# n-watch_v2_0_2022-03-19.net
KiCad netlist of a schematic drawn in Altium Designer
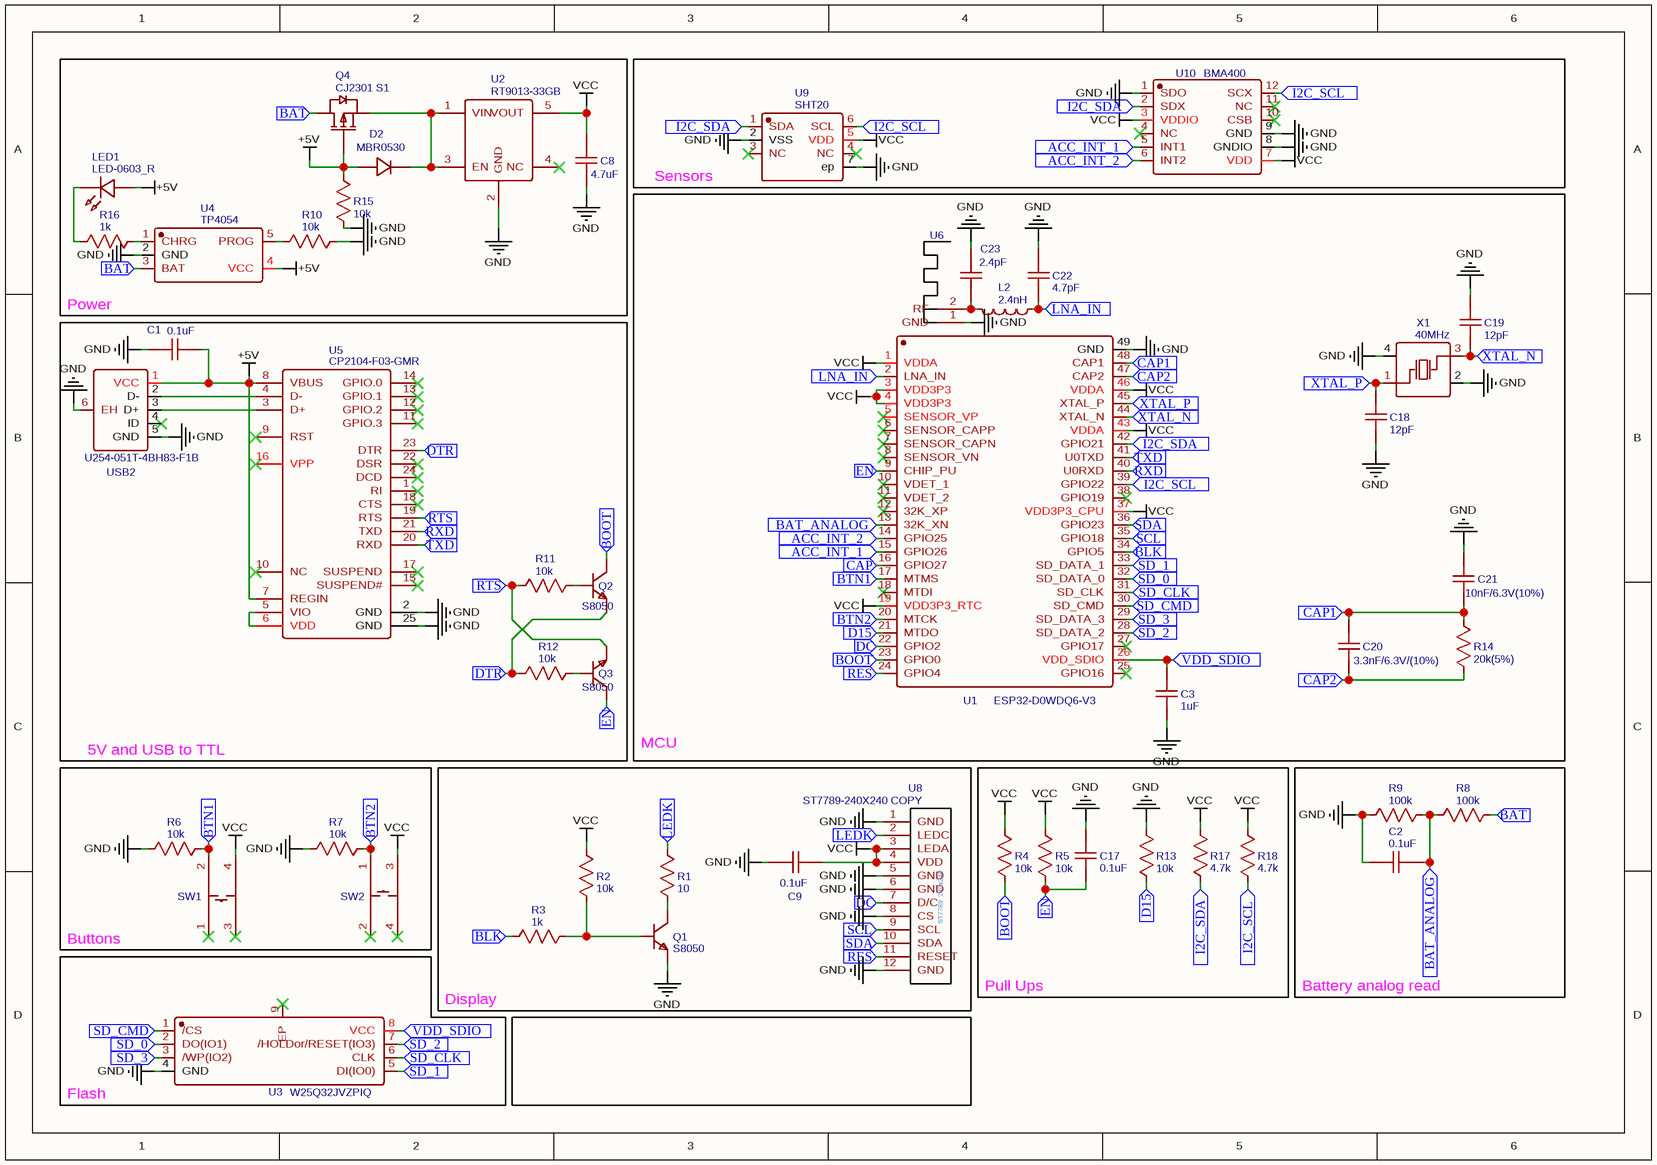
[diagram p0: n-watch v2.0_2022-03-19.schdoc]

(export (version "E")
  (design (tool "Eeschema 10.0.6"))
  (components
    (comp (ref "C1")
      (value "0.1uF")
      (fields (field (name "CONTRIBUTOR") "LCEDA_Lib"))
      (libsource (lib "altium-import") (part "root_2_0.1uF_"))
    )
    (comp (ref "C2")
      (value "0.1uF")
      (fields (field (name "CONTRIBUTOR") "LCEDA_Lib"))
      (libsource (lib "") (part "root_0_0.1uF__1"))
    )
    (comp (ref "C3")
      (value "1uF")
      (fields (field (name "CONTRIBUTOR") "LCEDA_Lib"))
      (libsource (lib "altium-import") (part "root_1_1uF_"))
    )
    (comp (ref "C8")
      (value "4.7uF")
      (fields (field (name "CONTRIBUTOR") "LCEDA_Lib"))
      (libsource (lib "altium-import") (part "root_1_4.7uF_"))
    )
    (comp (ref "C9")
      (value "0.1uF")
      (fields (field (name "CONTRIBUTOR") "LCEDA_Lib"))
      (libsource (lib "altium-import") (part "root_0_0.1uF_"))
    )
    (comp (ref "C17")
      (value "0.1uF")
      (fields (field (name "CONTRIBUTOR") "LCEDA_Lib"))
      (libsource (lib "altium-import") (part "root_1_0.1uF_"))
    )
    (comp (ref "C18")
      (value "12pF")
      (fields (field (name "CONTRIBUTOR") "LCEDA_Lib"))
      (libsource (lib "altium-import") (part "root_1_12pF_"))
    )
    (comp (ref "C19")
      (value "12pF")
      (fields (field (name "CONTRIBUTOR") "LCEDA_Lib"))
      (libsource (lib "altium-import") (part "root_1_12pF_"))
    )
    (comp (ref "C20")
      (value "3.3nF/6.3V/(10%)")
      (fields (field (name "CONTRIBUTOR") "LCEDA_Lib"))
      (libsource (lib "altium-import") (part "root_1_3.3nF/6.3V/(10%)_"))
    )
    (comp (ref "C21")
      (value "10nF/6.3V(10%)")
      (fields (field (name "CONTRIBUTOR") "LCEDA_Lib"))
      (libsource (lib "altium-import") (part "root_1_10nF/6.3V(10%)_"))
    )
    (comp (ref "C22")
      (value "4.7pF")
      (fields (field (name "CONTRIBUTOR") "LCEDA_Lib"))
      (libsource (lib "altium-import") (part "root_3_4.7pF_"))
    )
    (comp (ref "C23")
      (value "2.4pF")
      (fields (field (name "CONTRIBUTOR") "LCEDA_Lib"))
      (libsource (lib "altium-import") (part "root_1_2.4pF_"))
    )
    (comp (ref "D2")
      (value "MBR0530")
      (fields (field (name "BOM_SUPPLIER PART") "C77336"))
      (libsource (lib "altium-import") (part "root_2_MBR0530_"))
    )
    (comp (ref "L2")
      (value "2.4nH")
      (fields (field (name "CONTRIBUTOR") "LCEDA_Lib"))
      (libsource (lib "altium-import") (part "root_2_2.4nH_"))
    )
    (comp (ref "LED1")
      (value "LED-0603_R")
      (fields
        (field (name "BOM_MANUFACTURER PART") "19-217/R6C-AL1M2VY/3T")
        (field (name "BOM_SUPPLIER PART") "C72044")
        (field (name "CONTRIBUTOR") "LCEDA_01")
      )
      (libsource (lib "altium-import") (part "root_2_LED-0603_R_"))
    )
    (comp (ref "Q1")
      (value "S8050")
      (fields (field (name "BOM_SUPPLIER PART") "C916390") (field (name "CONTRIBUTOR") "LCSC"))
      (libsource (lib "altium-import") (part "root_0_S8050_"))
    )
    (comp (ref "Q2")
      (value "S8050")
      (fields (field (name "BOM_SUPPLIER PART") "C916390") (field (name "CONTRIBUTOR") "LCSC"))
      (libsource (lib "altium-import") (part "root_0_S8050_"))
    )
    (comp (ref "Q3")
      (value "S8050")
      (fields (field (name "BOM_SUPPLIER PART") "C916390") (field (name "CONTRIBUTOR") "LCSC"))
      (libsource (lib "") (part "root_0_S8050__1"))
    )
    (comp (ref "Q4")
      (value "CJ2301 S1")
      (fields (field (name "BOM_SUPPLIER PART") "C8547"))
      (libsource (lib "altium-import") (part "root_1_CJ2301 S1_"))
    )
    (comp (ref "R1")
      (value "10")
      (fields (field (name "CONTRIBUTOR") "LCEDA_Lib"))
      (libsource (lib "altium-import") (part "root_1_10_"))
    )
    (comp (ref "R2")
      (value "10k")
      (fields (field (name "CONTRIBUTOR") "LCEDA_Lib"))
      (libsource (lib "altium-import") (part "root_1_10k_"))
    )
    (comp (ref "R3")
      (value "1k")
      (fields (field (name "CONTRIBUTOR") "LCEDA_Lib"))
      (libsource (lib "altium-import") (part "root_2_1k_"))
    )
    (comp (ref "R4")
      (value "10k")
      (fields (field (name "CONTRIBUTOR") "LCEDA_Lib"))
      (libsource (lib "altium-import") (part "root_1_10k_"))
    )
    (comp (ref "R5")
      (value "10k")
      (fields (field (name "CONTRIBUTOR") "LCEDA_Lib"))
      (libsource (lib "altium-import") (part "root_1_10k_"))
    )
    (comp (ref "R6")
      (value "10k")
      (fields (field (name "CONTRIBUTOR") "LCEDA_Lib"))
      (libsource (lib "altium-import") (part "root_0_10k_"))
    )
    (comp (ref "R7")
      (value "10k")
      (fields (field (name "CONTRIBUTOR") "LCEDA_Lib"))
      (libsource (lib "altium-import") (part "root_0_10k_"))
    )
    (comp (ref "R8")
      (value "100k")
      (fields (field (name "CONTRIBUTOR") "LCEDA_Lib"))
      (libsource (lib "altium-import") (part "root_2_100k_"))
    )
    (comp (ref "R9")
      (value "100k")
      (fields (field (name "CONTRIBUTOR") "LCEDA_Lib"))
      (libsource (lib "altium-import") (part "root_2_100k_"))
    )
    (comp (ref "R10")
      (value "10k")
      (fields (field (name "CONTRIBUTOR") "LCEDA_Lib"))
      (libsource (lib "altium-import") (part "root_0_10k_"))
    )
    (comp (ref "R11")
      (value "10k")
      (fields (field (name "CONTRIBUTOR") "LCEDA_Lib"))
      (libsource (lib "altium-import") (part "root_2_10k_"))
    )
    (comp (ref "R12")
      (value "10k")
      (fields (field (name "CONTRIBUTOR") "LCEDA_Lib"))
      (libsource (lib "altium-import") (part "root_0_10k_"))
    )
    (comp (ref "R13")
      (value "10k")
      (fields (field (name "CONTRIBUTOR") "LCEDA_Lib"))
      (libsource (lib "altium-import") (part "root_1_10k_"))
    )
    (comp (ref "R14")
      (value "20k(5%)")
      (fields (field (name "CONTRIBUTOR") "LCEDA_Lib"))
      (libsource (lib "altium-import") (part "root_1_20k(5%)_"))
    )
    (comp (ref "R15")
      (value "10k")
      (fields (field (name "CONTRIBUTOR") "LCEDA_Lib"))
      (libsource (lib "altium-import") (part "root_1_10k_"))
    )
    (comp (ref "R16")
      (value "1k")
      (fields (field (name "CONTRIBUTOR") "LCEDA_Lib"))
      (libsource (lib "altium-import") (part "root_0_1k_"))
    )
    (comp (ref "R17")
      (value "4.7k")
      (fields (field (name "CONTRIBUTOR") "LCEDA_Lib"))
      (libsource (lib "altium-import") (part "root_1_4.7k_"))
    )
    (comp (ref "R18")
      (value "4.7k")
      (fields (field (name "CONTRIBUTOR") "LCEDA_Lib"))
      (libsource (lib "altium-import") (part "root_1_4.7k_"))
    )
    (comp (ref "SW1")
      (value "K2-1114SA-A4SW-06")
      (fields (field (name "BOM_SUPPLIER PART") "C136662") (field (name "CONTRIBUTOR") "LCSC"))
      (libsource (lib "altium-import") (part "root_1_K2-1114SA-A4SW-06_"))
    )
    (comp (ref "SW2")
      (value "K2-1114SA-A4SW-06")
      (fields (field (name "BOM_SUPPLIER PART") "C136662") (field (name "CONTRIBUTOR") "LCSC"))
      (libsource (lib "altium-import") (part "root_3_K2-1114SA-A4SW-06_"))
    )
    (comp (ref "U1")
      (value "ESP32-D0WDQ6-V3")
      (fields (field (name "BOM_SUPPLIER PART") "C967020") (field (name "CONTRIBUTOR") "LCSC"))
      (libsource (lib "altium-import") (part "root_0_ESP32-D0WDQ6-V3_"))
    )
    (comp (ref "U2")
      (value "RT9013-33GB")
      (fields (field (name "BOM_SUPPLIER PART") "C47773") (field (name "CONTRIBUTOR") "catech75"))
      (libsource (lib "altium-import") (part "root_0_RT9013-33GB_"))
    )
    (comp (ref "U3")
      (value "W25Q32JVZPIQ")
      (fields (field (name "BOM_SUPPLIER PART") "C571260") (field (name "CONTRIBUTOR") "LCSC"))
      (libsource (lib "altium-import") (part "root_0_W25Q32JVZPIQ_"))
    )
    (comp (ref "U4")
      (value "TP4054")
      (fields (field (name "BOM_SUPPLIER PART") "C32574") (field (name "CONTRIBUTOR") "kyle.hu.gz"))
      (libsource (lib "altium-import") (part "root_0_TP4054_"))
    )
    (comp (ref "U5")
      (value "CP2104-F03-GMR")
      (fields (field (name "BOM_SUPPLIER PART") "C47015") (field (name "CONTRIBUTOR") "LCSC"))
      (libsource (lib "altium-import") (part "root_0_CP2104-F03-GMR_"))
    )
    (comp (ref "U6")
      (value "PCB ANTENNA 2.4GHZ UNDER MASK")
      (fields (field (name "CONTRIBUTOR") "matuhinmax"))
      (libsource (lib "altium-import") (part "root_1_PCB ANTENNA 2.4GHZ UNDER MASK_"))
    )
    (comp (ref "U8")
      (value "ST7789-240X240 COPY")
      (fields (field (name "CONTRIBUTOR") "peut"))
      (libsource (lib "altium-import") (part "root_0_ST7789-240X240 COPY_"))
    )
    (comp (ref "U9")
      (value "SHT20")
      (fields (field (name "BOM_SUPPLIER PART") "C53865"))
      (libsource (lib "altium-import") (part "root_0_SHT20_"))
    )
    (comp (ref "U10")
      (value "BMA400")
      (fields (field (name "BOM_SUPPLIER PART") "C437655") (field (name "CONTRIBUTOR") "LCSC"))
      (libsource (lib "altium-import") (part "root_0_BMA400_"))
    )
    (comp (ref "USB2")
      (value "U254-051T-4BH83-F1B")
      (fields (field (name "BOM_SUPPLIER PART") "C319162") (field (name "CONTRIBUTOR") "LCSC"))
      (libsource (lib "altium-import") (part "root_2_U254-051T-4BH83-F1B_"))
    )
    (comp (ref "X1")
      (value "40MHz")
      (fields
        (field (name "BOM_SUPPLIER PART") "C337678")
        (field (name "BOM_MANUFACTURER PART") "3225-40M-12PF-10PPM")
        (field (name "CONTRIBUTOR") "LCSC")
      )
      (libsource (lib "altium-import") (part "root_0_40MHz_"))
    )
  )
  (nets
    (net (code "1") (name "+5V") (class "Default")
      (node (ref "C1") (pin "1") (pinfunction "1_1") (pintype "passive"))
      (node (ref "D2") (pin "2") (pinfunction "A_2") (pintype "passive"))
      (node (ref "LED1") (pin "1") (pinfunction "1_1") (pintype "passive"))
      (node (ref "Q4") (pin "1") (pinfunction "G_1") (pintype "passive"))
      (node (ref "R15") (pin "2") (pinfunction "2_2") (pintype "passive"))
      (node (ref "U4") (pin "4") (pinfunction "VCC_4") (pintype "passive"))
      (node (ref "U5") (pin "7") (pinfunction "REGIN_7") (pintype "passive"))
      (node (ref "U5") (pin "8") (pinfunction "VBUS_8") (pintype "passive"))
      (node (ref "USB2") (pin "1") (pinfunction "VCC_1") (pintype "passive"))
    )
    (net (code "2") (name "/ACC_INT_1") (class "Default")
      (node (ref "U1") (pin "15") (pinfunction "GPIO26_15") (pintype "passive"))
      (node (ref "U10") (pin "5") (pinfunction "INT1_5") (pintype "passive"))
    )
    (net (code "3") (name "/ACC_INT_2") (class "Default")
      (node (ref "U1") (pin "14") (pinfunction "GPIO25_14") (pintype "passive"))
      (node (ref "U10") (pin "6") (pinfunction "INT2_6") (pintype "passive"))
    )
    (net (code "4") (name "/BAT") (class "Default")
      (node (ref "Q4") (pin "3") (pinfunction "D_3") (pintype "passive"))
      (node (ref "R8") (pin "1") (pinfunction "1_1") (pintype "passive"))
      (node (ref "U4") (pin "3") (pinfunction "BAT_3") (pintype "passive"))
    )
    (net (code "5") (name "/BAT_ANALOG") (class "Default")
      (node (ref "C2") (pin "2") (pinfunction "2_2") (pintype "passive"))
      (node (ref "R8") (pin "2") (pinfunction "2_2") (pintype "passive"))
      (node (ref "R9") (pin "1") (pinfunction "1_1") (pintype "passive"))
      (node (ref "U1") (pin "13") (pinfunction "32K_XN_13") (pintype "passive"))
    )
    (net (code "6") (name "/BLK") (class "Default")
      (node (ref "R3") (pin "2") (pinfunction "2_2") (pintype "passive"))
      (node (ref "U1") (pin "34") (pinfunction "GPIO5_34") (pintype "passive"))
    )
    (net (code "7") (name "/BOOT") (class "Default")
      (node (ref "Q2") (pin "3") (pinfunction "C_3") (pintype "passive"))
      (node (ref "R4") (pin "1") (pinfunction "1_1") (pintype "passive"))
      (node (ref "U1") (pin "23") (pinfunction "GPIO0_23") (pintype "passive"))
    )
    (net (code "8") (name "/BTN1") (class "Default")
      (node (ref "R6") (pin "2") (pinfunction "2_2") (pintype "passive"))
      (node (ref "SW1") (pin "2") (pinfunction "2_2") (pintype "passive"))
      (node (ref "U1") (pin "17") (pinfunction "MTMS_17") (pintype "passive"))
    )
    (net (code "9") (name "/BTN2") (class "Default")
      (node (ref "R7") (pin "2") (pinfunction "2_2") (pintype "passive"))
      (node (ref "SW2") (pin "1") (pinfunction "1_1") (pintype "passive"))
      (node (ref "U1") (pin "20") (pinfunction "MTCK_20") (pintype "passive"))
    )
    (net (code "10") (name "/CAP") (class "Default")
      (node (ref "U1") (pin "16") (pinfunction "GPIO27_16") (pintype "passive"))
    )
    (net (code "11") (name "/CAP1") (class "Default")
      (node (ref "C20") (pin "2") (pinfunction "2_2") (pintype "passive"))
      (node (ref "C21") (pin "1") (pinfunction "1_1") (pintype "passive"))
      (node (ref "R14") (pin "2") (pinfunction "2_2") (pintype "passive"))
      (node (ref "U1") (pin "48") (pinfunction "CAP1_48") (pintype "passive"))
    )
    (net (code "12") (name "/CAP2") (class "Default")
      (node (ref "C20") (pin "1") (pinfunction "1_1") (pintype "passive"))
      (node (ref "R14") (pin "1") (pinfunction "1_1") (pintype "passive"))
      (node (ref "U1") (pin "47") (pinfunction "CAP2_47") (pintype "passive"))
    )
    (net (code "13") (name "/D15") (class "Default")
      (node (ref "R13") (pin "1") (pinfunction "1_1") (pintype "passive"))
      (node (ref "U1") (pin "21") (pinfunction "MTDO_21") (pintype "passive"))
    )
    (net (code "14") (name "/DC") (class "Default")
      (node (ref "U1") (pin "22") (pinfunction "GPIO2_22") (pintype "passive"))
      (node (ref "U8") (pin "7") (pinfunction "D/C_7") (pintype "passive"))
    )
    (net (code "15") (name "/DTR") (class "Default")
      (node (ref "Q2") (pin "2") (pinfunction "E_2") (pintype "passive"))
      (node (ref "R12") (pin "1") (pinfunction "1_1") (pintype "passive"))
      (node (ref "U5") (pin "23") (pinfunction "DTR_23") (pintype "passive"))
    )
    (net (code "16") (name "/EN") (class "Default")
      (node (ref "C17") (pin "1") (pinfunction "1_1") (pintype "passive"))
      (node (ref "Q3") (pin "3") (pinfunction "C_3") (pintype "passive"))
      (node (ref "R5") (pin "1") (pinfunction "1_1") (pintype "passive"))
      (node (ref "U1") (pin "9") (pinfunction "CHIP_PU_9") (pintype "passive"))
    )
    (net (code "17") (name "/I2C_SCL") (class "Default")
      (node (ref "R18") (pin "1") (pinfunction "1_1") (pintype "passive"))
      (node (ref "U1") (pin "39") (pinfunction "GPIO22_39") (pintype "passive"))
      (node (ref "U10") (pin "12") (pinfunction "SCX_12") (pintype "passive"))
      (node (ref "U9") (pin "6") (pinfunction "SCL_6") (pintype "passive"))
    )
    (net (code "18") (name "/I2C_SDA") (class "Default")
      (node (ref "R17") (pin "1") (pinfunction "1_1") (pintype "passive"))
      (node (ref "U1") (pin "42") (pinfunction "GPIO21_42") (pintype "passive"))
      (node (ref "U10") (pin "2") (pinfunction "SDX_2") (pintype "passive"))
      (node (ref "U9") (pin "1") (pinfunction "SDA_1") (pintype "passive"))
    )
    (net (code "19") (name "/LEDK") (class "Default")
      (node (ref "R1") (pin "2") (pinfunction "2_2") (pintype "passive"))
      (node (ref "U8") (pin "2") (pinfunction "LEDC_2") (pintype "passive"))
    )
    (net (code "20") (name "/LNA_IN") (class "Default")
      (node (ref "C22") (pin "2") (pinfunction "2_2") (pintype "passive"))
      (node (ref "L2") (pin "1") (pinfunction "1_1") (pintype "passive"))
      (node (ref "U1") (pin "2") (pinfunction "LNA_IN_2") (pintype "passive"))
    )
    (net (code "21") (name "/RES") (class "Default")
      (node (ref "U1") (pin "24") (pinfunction "GPIO4_24") (pintype "passive"))
      (node (ref "U8") (pin "11") (pinfunction "RESET_11") (pintype "passive"))
    )
    (net (code "22") (name "/RTS") (class "Default")
      (node (ref "Q3") (pin "2") (pinfunction "E_2") (pintype "passive"))
      (node (ref "R11") (pin "2") (pinfunction "2_2") (pintype "passive"))
      (node (ref "U5") (pin "19") (pinfunction "RTS_19") (pintype "passive"))
    )
    (net (code "23") (name "/RXD") (class "Default")
      (node (ref "U1") (pin "40") (pinfunction "U0RXD_40") (pintype "passive"))
      (node (ref "U5") (pin "21") (pinfunction "TXD_21") (pintype "passive"))
    )
    (net (code "24") (name "/SCL") (class "Default")
      (node (ref "U1") (pin "35") (pinfunction "GPIO18_35") (pintype "passive"))
      (node (ref "U8") (pin "9") (pinfunction "SCL_9") (pintype "passive"))
    )
    (net (code "25") (name "/SDA") (class "Default")
      (node (ref "U1") (pin "36") (pinfunction "GPIO23_36") (pintype "passive"))
      (node (ref "U8") (pin "10") (pinfunction "SDA_10") (pintype "passive"))
    )
    (net (code "26") (name "/SD_0") (class "Default")
      (node (ref "U1") (pin "32") (pinfunction "SD_DATA_0_32") (pintype "passive"))
      (node (ref "U3") (pin "2") (pinfunction "DO(IO1)_2") (pintype "passive"))
    )
    (net (code "27") (name "/SD_1") (class "Default")
      (node (ref "U1") (pin "33") (pinfunction "SD_DATA_1_33") (pintype "passive"))
      (node (ref "U3") (pin "5") (pinfunction "DI(IO0)_5") (pintype "passive"))
    )
    (net (code "28") (name "/SD_2") (class "Default")
      (node (ref "U1") (pin "28") (pinfunction "SD_DATA_2_28") (pintype "passive"))
      (node (ref "U3") (pin "7") (pinfunction "/HOLDor/RESET(IO3)_7") (pintype "passive"))
    )
    (net (code "29") (name "/SD_3") (class "Default")
      (node (ref "U1") (pin "29") (pinfunction "SD_DATA_3_29") (pintype "passive"))
      (node (ref "U3") (pin "3") (pinfunction "/WP(IO2)_3") (pintype "passive"))
    )
    (net (code "30") (name "/SD_CLK") (class "Default")
      (node (ref "U1") (pin "31") (pinfunction "SD_CLK_31") (pintype "passive"))
      (node (ref "U3") (pin "6") (pinfunction "CLK_6") (pintype "passive"))
    )
    (net (code "31") (name "/SD_CMD") (class "Default")
      (node (ref "U1") (pin "30") (pinfunction "SD_CMD_30") (pintype "passive"))
      (node (ref "U3") (pin "1") (pinfunction "/CS_1") (pintype "passive"))
    )
    (net (code "32") (name "/TXD") (class "Default")
      (node (ref "U1") (pin "41") (pinfunction "U0TXD_41") (pintype "passive"))
      (node (ref "U5") (pin "20") (pinfunction "RXD_20") (pintype "passive"))
    )
    (net (code "33") (name "/VDD_SDIO") (class "Default")
      (node (ref "C3") (pin "2") (pinfunction "2_2") (pintype "passive"))
      (node (ref "U1") (pin "26") (pinfunction "VDD_SDIO_26") (pintype "passive"))
      (node (ref "U3") (pin "8") (pinfunction "VCC_8") (pintype "passive"))
    )
    (net (code "34") (name "/XTAL_N") (class "Default")
      (node (ref "C19") (pin "1") (pinfunction "1_1") (pintype "passive"))
      (node (ref "U1") (pin "44") (pinfunction "XTAL_N_44") (pintype "passive"))
      (node (ref "X1") (pin "3") (pinfunction "OSC2_3") (pintype "passive"))
    )
    (net (code "35") (name "/XTAL_P") (class "Default")
      (node (ref "C18") (pin "2") (pinfunction "2_2") (pintype "passive"))
      (node (ref "U1") (pin "45") (pinfunction "XTAL_P_45") (pintype "passive"))
      (node (ref "X1") (pin "1") (pinfunction "OSC1_1") (pintype "passive"))
    )
    (net (code "36") (name "GND") (class "Default")
      (node (ref "C1") (pin "2") (pinfunction "2_2") (pintype "passive"))
      (node (ref "C17") (pin "2") (pinfunction "2_2") (pintype "passive"))
      (node (ref "C18") (pin "1") (pinfunction "1_1") (pintype "passive"))
      (node (ref "C19") (pin "2") (pinfunction "2_2") (pintype "passive"))
      (node (ref "C2") (pin "1") (pinfunction "1_1") (pintype "passive"))
      (node (ref "C21") (pin "2") (pinfunction "2_2") (pintype "passive"))
      (node (ref "C22") (pin "1") (pinfunction "1_1") (pintype "passive"))
      (node (ref "C23") (pin "2") (pinfunction "2_2") (pintype "passive"))
      (node (ref "C3") (pin "1") (pinfunction "1_1") (pintype "passive"))
      (node (ref "C8") (pin "1") (pinfunction "1_1") (pintype "passive"))
      (node (ref "C9") (pin "1") (pinfunction "1_1") (pintype "passive"))
      (node (ref "Q1") (pin "2") (pinfunction "E_2") (pintype "passive"))
      (node (ref "R10") (pin "2") (pinfunction "2_2") (pintype "passive"))
      (node (ref "R13") (pin "2") (pinfunction "2_2") (pintype "passive"))
      (node (ref "R15") (pin "1") (pinfunction "1_1") (pintype "passive"))
      (node (ref "R6") (pin "1") (pinfunction "1_1") (pintype "passive"))
      (node (ref "R7") (pin "1") (pinfunction "1_1") (pintype "passive"))
      (node (ref "R9") (pin "2") (pinfunction "2_2") (pintype "passive"))
      (node (ref "U1") (pin "49") (pinfunction "GND_49") (pintype "passive"))
      (node (ref "U10") (pin "1") (pinfunction "SDO_1") (pintype "passive"))
      (node (ref "U10") (pin "8") (pinfunction "GNDIO_8") (pintype "passive"))
      (node (ref "U10") (pin "9") (pinfunction "GND_9") (pintype "passive"))
      (node (ref "U2") (pin "2") (pinfunction "GND_2") (pintype "passive"))
      (node (ref "U3") (pin "4") (pinfunction "GND_4") (pintype "passive"))
      (node (ref "U4") (pin "2") (pinfunction "GND_2") (pintype "passive"))
      (node (ref "U5") (pin "2") (pinfunction "GND_2") (pintype "passive"))
      (node (ref "U5") (pin "25") (pinfunction "GND_25") (pintype "passive"))
      (node (ref "U6") (pin "1") (pinfunction "GND_1") (pintype "passive"))
      (node (ref "U8") (pin "1") (pinfunction "GND_1") (pintype "passive"))
      (node (ref "U8") (pin "12") (pinfunction "GND_12") (pintype "passive"))
      (node (ref "U8") (pin "5") (pinfunction "GND_5") (pintype "passive"))
      (node (ref "U8") (pin "6") (pinfunction "GND_6") (pintype "passive"))
      (node (ref "U8") (pin "8") (pinfunction "CS_8") (pintype "passive"))
      (node (ref "U9") (pin "2") (pinfunction "VSS_2") (pintype "passive"))
      (node (ref "U9") (pin "7") (pinfunction "ep_7") (pintype "passive"))
      (node (ref "USB2") (pin "5") (pinfunction "GND_5") (pintype "passive"))
      (node (ref "USB2") (pin "6") (pinfunction "EH_6") (pintype "passive"))
      (node (ref "X1") (pin "2") (pinfunction "GND_2") (pintype "passive"))
      (node (ref "X1") (pin "4") (pinfunction "GND_4") (pintype "passive"))
    )
    (net (code "37") (name "Net-(D2-C)") (class "Default")
      (node (ref "D2") (pin "1") (pinfunction "C_1") (pintype "passive"))
      (node (ref "Q4") (pin "2") (pinfunction "S_2") (pintype "passive"))
      (node (ref "U2") (pin "1") (pinfunction "VIN_1") (pintype "passive"))
      (node (ref "U2") (pin "3") (pinfunction "EN_3") (pintype "passive"))
    )
    (net (code "38") (name "Net-(LED1-Pad2)") (class "Default")
      (node (ref "LED1") (pin "2") (pinfunction "2_2") (pintype "passive"))
      (node (ref "R16") (pin "1") (pinfunction "1_1") (pintype "passive"))
    )
    (net (code "39") (name "Net-(Q1-B)") (class "Default")
      (node (ref "Q1") (pin "1") (pinfunction "B_1") (pintype "passive"))
      (node (ref "R2") (pin "1") (pinfunction "1_1") (pintype "passive"))
      (node (ref "R3") (pin "1") (pinfunction "1_1") (pintype "passive"))
    )
    (net (code "40") (name "Net-(Q1-C)") (class "Default")
      (node (ref "Q1") (pin "3") (pinfunction "C_3") (pintype "passive"))
      (node (ref "R1") (pin "1") (pinfunction "1_1") (pintype "passive"))
    )
    (net (code "41") (name "Net-(Q2-B)") (class "Default")
      (node (ref "Q2") (pin "1") (pinfunction "B_1") (pintype "passive"))
      (node (ref "R11") (pin "1") (pinfunction "1_1") (pintype "passive"))
    )
    (net (code "42") (name "Net-(Q3-B)") (class "Default")
      (node (ref "Q3") (pin "1") (pinfunction "B_1") (pintype "passive"))
      (node (ref "R12") (pin "2") (pinfunction "2_2") (pintype "passive"))
    )
    (net (code "43") (name "Net-(U4-CHRG)") (class "Default")
      (node (ref "R16") (pin "2") (pinfunction "2_2") (pintype "passive"))
      (node (ref "U4") (pin "1") (pinfunction "CHRG_1") (pintype "passive"))
    )
    (net (code "44") (name "Net-(U4-PROG)") (class "Default")
      (node (ref "R10") (pin "1") (pinfunction "1_1") (pintype "passive"))
      (node (ref "U4") (pin "5") (pinfunction "PROG_5") (pintype "passive"))
    )
    (net (code "45") (name "Net-(U5-D+)") (class "Default")
      (node (ref "U5") (pin "3") (pinfunction "D+_3") (pintype "passive"))
      (node (ref "USB2") (pin "3") (pinfunction "D+_3") (pintype "passive"))
    )
    (net (code "46") (name "Net-(U5-D-)") (class "Default")
      (node (ref "U5") (pin "4") (pinfunction "D-_4") (pintype "passive"))
      (node (ref "USB2") (pin "2") (pinfunction "D-_2") (pintype "passive"))
    )
    (net (code "47") (name "Net-(U5-VDD)") (class "Default")
      (node (ref "U5") (pin "5") (pinfunction "VIO_5") (pintype "passive"))
      (node (ref "U5") (pin "6") (pinfunction "VDD_6") (pintype "passive"))
    )
    (net (code "48") (name "Net-(U6-RF)") (class "Default")
      (node (ref "C23") (pin "1") (pinfunction "1_1") (pintype "passive"))
      (node (ref "L2") (pin "2") (pinfunction "2_2") (pintype "passive"))
      (node (ref "U6") (pin "2") (pinfunction "RF_2") (pintype "passive"))
    )
    (net (code "49") (name "VCC") (class "Default")
      (node (ref "C8") (pin "2") (pinfunction "2_2") (pintype "passive"))
      (node (ref "C9") (pin "2") (pinfunction "2_2") (pintype "passive"))
      (node (ref "R17") (pin "2") (pinfunction "2_2") (pintype "passive"))
      (node (ref "R18") (pin "2") (pinfunction "2_2") (pintype "passive"))
      (node (ref "R2") (pin "2") (pinfunction "2_2") (pintype "passive"))
      (node (ref "R4") (pin "2") (pinfunction "2_2") (pintype "passive"))
      (node (ref "R5") (pin "2") (pinfunction "2_2") (pintype "passive"))
      (node (ref "SW1") (pin "4") (pinfunction "4_4") (pintype "passive"))
      (node (ref "SW2") (pin "3") (pinfunction "3_3") (pintype "passive"))
      (node (ref "U1") (pin "1") (pinfunction "VDDA_1") (pintype "passive"))
      (node (ref "U1") (pin "19") (pinfunction "VDD3P3_RTC_19") (pintype "passive"))
      (node (ref "U1") (pin "3") (pinfunction "VDD3P3_3") (pintype "passive"))
      (node (ref "U1") (pin "37") (pinfunction "VDD3P3_CPU_37") (pintype "passive"))
      (node (ref "U1") (pin "4") (pinfunction "VDD3P3_4") (pintype "passive"))
      (node (ref "U1") (pin "43") (pinfunction "VDDA_43") (pintype "passive"))
      (node (ref "U1") (pin "46") (pinfunction "VDDA_46") (pintype "passive"))
      (node (ref "U10") (pin "3") (pinfunction "VDDIO_3") (pintype "passive"))
      (node (ref "U10") (pin "7") (pinfunction "VDD_7") (pintype "passive"))
      (node (ref "U2") (pin "5") (pinfunction "VOUT_5") (pintype "passive"))
      (node (ref "U8") (pin "3") (pinfunction "LEDA_3") (pintype "passive"))
      (node (ref "U8") (pin "4") (pinfunction "VDD_4") (pintype "passive"))
      (node (ref "U9") (pin "5") (pinfunction "VDD_5") (pintype "passive"))
    )
    (net (code "50") (name "unconnected-(SW1-Pad1)") (class "Default")
      (node (ref "SW1") (pin "1") (pinfunction "1_1") (pintype "passive+no_connect"))
    )
    (net (code "51") (name "unconnected-(SW1-Pad3)") (class "Default")
      (node (ref "SW1") (pin "3") (pinfunction "3_3") (pintype "passive+no_connect"))
    )
    (net (code "52") (name "unconnected-(SW2-Pad2)") (class "Default")
      (node (ref "SW2") (pin "2") (pinfunction "2_2") (pintype "passive+no_connect"))
    )
    (net (code "53") (name "unconnected-(SW2-Pad4)") (class "Default")
      (node (ref "SW2") (pin "4") (pinfunction "4_4") (pintype "passive+no_connect"))
    )
    (net (code "54") (name "unconnected-(U1-32K_XP-Pad12)") (class "Default")
      (node (ref "U1") (pin "12") (pinfunction "32K_XP_12") (pintype "passive+no_connect"))
    )
    (net (code "55") (name "unconnected-(U1-GPIO16-Pad25)") (class "Default")
      (node (ref "U1") (pin "25") (pinfunction "GPIO16_25") (pintype "passive+no_connect"))
    )
    (net (code "56") (name "unconnected-(U1-GPIO17-Pad27)") (class "Default")
      (node (ref "U1") (pin "27") (pinfunction "GPIO17_27") (pintype "passive+no_connect"))
    )
    (net (code "57") (name "unconnected-(U1-GPIO19-Pad38)") (class "Default")
      (node (ref "U1") (pin "38") (pinfunction "GPIO19_38") (pintype "passive+no_connect"))
    )
    (net (code "58") (name "unconnected-(U1-MTDI-Pad18)") (class "Default")
      (node (ref "U1") (pin "18") (pinfunction "MTDI_18") (pintype "passive+no_connect"))
    )
    (net (code "59") (name "unconnected-(U1-SENSOR_CAPN-Pad7)") (class "Default")
      (node (ref "U1") (pin "7") (pinfunction "SENSOR_CAPN_7") (pintype "passive+no_connect"))
    )
    (net (code "60") (name "unconnected-(U1-SENSOR_CAPP-Pad6)") (class "Default")
      (node (ref "U1") (pin "6") (pinfunction "SENSOR_CAPP_6") (pintype "passive+no_connect"))
    )
    (net (code "61") (name "unconnected-(U1-SENSOR_VN-Pad8)") (class "Default")
      (node (ref "U1") (pin "8") (pinfunction "SENSOR_VN_8") (pintype "passive+no_connect"))
    )
    (net (code "62") (name "unconnected-(U1-SENSOR_VP-Pad5)") (class "Default")
      (node (ref "U1") (pin "5") (pinfunction "SENSOR_VP_5") (pintype "passive+no_connect"))
    )
    (net (code "63") (name "unconnected-(U1-VDET_1-Pad10)") (class "Default")
      (node (ref "U1") (pin "10") (pinfunction "VDET_1_10") (pintype "passive+no_connect"))
    )
    (net (code "64") (name "unconnected-(U1-VDET_2-Pad11)") (class "Default")
      (node (ref "U1") (pin "11") (pinfunction "VDET_2_11") (pintype "passive+no_connect"))
    )
    (net (code "65") (name "unconnected-(U2-NC-Pad4)") (class "Default")
      (node (ref "U2") (pin "4") (pinfunction "NC_4") (pintype "passive+no_connect"))
    )
    (net (code "66") (name "unconnected-(U3-EP-Pad9)") (class "Default")
      (node (ref "U3") (pin "9") (pinfunction "EP_9") (pintype "passive+no_connect"))
    )
    (net (code "67") (name "unconnected-(U5-CTS-Pad18)") (class "Default")
      (node (ref "U5") (pin "18") (pinfunction "CTS_18") (pintype "passive+no_connect"))
    )
    (net (code "68") (name "unconnected-(U5-DCD-Pad24)") (class "Default")
      (node (ref "U5") (pin "24") (pinfunction "DCD_24") (pintype "passive+no_connect"))
    )
    (net (code "69") (name "unconnected-(U5-DSR-Pad22)") (class "Default")
      (node (ref "U5") (pin "22") (pinfunction "DSR_22") (pintype "passive+no_connect"))
    )
    (net (code "70") (name "unconnected-(U5-GPIO.0-Pad14)") (class "Default")
      (node (ref "U5") (pin "14") (pinfunction "GPIO.0_14") (pintype "passive+no_connect"))
    )
    (net (code "71") (name "unconnected-(U5-GPIO.1-Pad13)") (class "Default")
      (node (ref "U5") (pin "13") (pinfunction "GPIO.1_13") (pintype "passive+no_connect"))
    )
    (net (code "72") (name "unconnected-(U5-GPIO.2-Pad12)") (class "Default")
      (node (ref "U5") (pin "12") (pinfunction "GPIO.2_12") (pintype "passive+no_connect"))
    )
    (net (code "73") (name "unconnected-(U5-GPIO.3-Pad11)") (class "Default")
      (node (ref "U5") (pin "11") (pinfunction "GPIO.3_11") (pintype "passive+no_connect"))
    )
    (net (code "74") (name "unconnected-(U5-NC-Pad10)") (class "Default")
      (node (ref "U5") (pin "10") (pinfunction "NC_10") (pintype "passive+no_connect"))
    )
    (net (code "75") (name "unconnected-(U5-RI-Pad1)") (class "Default")
      (node (ref "U5") (pin "1") (pinfunction "RI_1") (pintype "passive+no_connect"))
    )
    (net (code "76") (name "unconnected-(U5-RST-Pad9)") (class "Default")
      (node (ref "U5") (pin "9") (pinfunction "RST_9") (pintype "passive+no_connect"))
    )
    (net (code "77") (name "unconnected-(U5-SUSPEND#-Pad15)") (class "Default")
      (node (ref "U5") (pin "15") (pinfunction "SUSPEND#_15") (pintype "passive+no_connect"))
    )
    (net (code "78") (name "unconnected-(U5-SUSPEND-Pad17)") (class "Default")
      (node (ref "U5") (pin "17") (pinfunction "SUSPEND_17") (pintype "passive+no_connect"))
    )
    (net (code "79") (name "unconnected-(U5-VPP-Pad16)") (class "Default")
      (node (ref "U5") (pin "16") (pinfunction "VPP_16") (pintype "passive+no_connect"))
    )
    (net (code "80") (name "unconnected-(U9-NC-Pad3)") (class "Default")
      (node (ref "U9") (pin "3") (pinfunction "NC_3") (pintype "passive+no_connect"))
    )
    (net (code "81") (name "unconnected-(U9-NC-Pad4)") (class "Default")
      (node (ref "U9") (pin "4") (pinfunction "NC_4") (pintype "passive+no_connect"))
    )
    (net (code "82") (name "unconnected-(U10-CSB-Pad10)") (class "Default")
      (node (ref "U10") (pin "10") (pinfunction "CSB_10") (pintype "passive+no_connect"))
    )
    (net (code "83") (name "unconnected-(U10-NC-Pad4)") (class "Default")
      (node (ref "U10") (pin "4") (pinfunction "NC_4") (pintype "passive+no_connect"))
    )
    (net (code "84") (name "unconnected-(U10-NC-Pad11)") (class "Default")
      (node (ref "U10") (pin "11") (pinfunction "NC_11") (pintype "passive+no_connect"))
    )
    (net (code "85") (name "unconnected-(USB2-ID-Pad4)") (class "Default")
      (node (ref "USB2") (pin "4") (pinfunction "ID_4") (pintype "passive+no_connect"))
    )
  )
)
